# Sheet3.net
KiCad netlist of a schematic drawn in Altium Designer
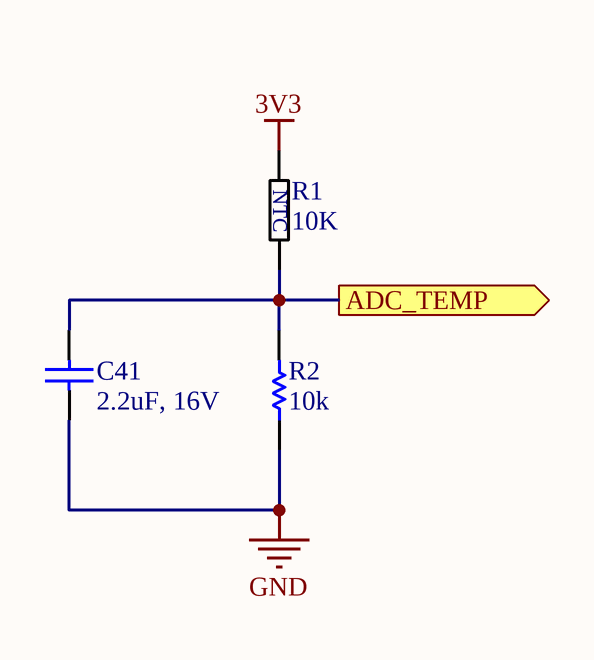
[diagram p0: Sheet3.SchDoc]

(export (version "E")
  (design (tool "Eeschema 10.0.6"))
  (components
    (comp (ref "C41")
      (value "2.2uF, 16V")
      (footprint "SMD-0603 Capacitor")
      (description "CAP 2.2u, 16V, 0603")
      (fields
        (field (name "MANUFACTURER PART NUMBER") "C1608X5R1C225M")
        (field (name "MANUFACTURER") "TDK Corporation")
      )
      (libsource (lib "Master Data Link") (part "CAP"))
    )
    (comp (ref "R1")
      (value "10K")
      (footprint "SMD-0603 Resistor")
      (description "NTC resistor (temp sensor)")
      (fields
        (field (name "MANUFACTURER PART NUMBER") "NCP18XH103F03RB")
        (field (name "MANUFACTURER") "Murata Electronics North America")
      )
      (libsource (lib "Master Data Link") (part "NTC"))
    )
    (comp (ref "R2")
      (value "10k")
      (footprint "SMD-0603 Resistor")
      (description "R 10k, 0603")
      (fields
        (field (name "MANUFACTURER PART NUMBER") "RK73H1JTTD1002F")
        (field (name "MANUFACTURER") "KOA Speer")
      )
      (libsource (lib "Master Data Link") (part "RES"))
    )
  )
  (nets
    (net (code "1") (name "/ADC_TEMP") (class "Default")
      (node (ref "C41") (pin "2") (pinfunction "2_2") (pintype "passive"))
      (node (ref "R1") (pin "1") (pinfunction "1_1") (pintype "passive"))
      (node (ref "R2") (pin "2") (pinfunction "2_2") (pintype "passive"))
    )
    (net (code "2") (name "3V3") (class "Default")
      (node (ref "R1") (pin "2") (pinfunction "2_2") (pintype "passive"))
    )
    (net (code "3") (name "GND") (class "Default")
      (node (ref "C41") (pin "1") (pinfunction "1_1") (pintype "passive"))
      (node (ref "R2") (pin "1") (pinfunction "1_1") (pintype "passive"))
    )
  )
)
